# P4-Temperatura_LM35.net
KiCad netlist of a schematic drawn in EAGLE
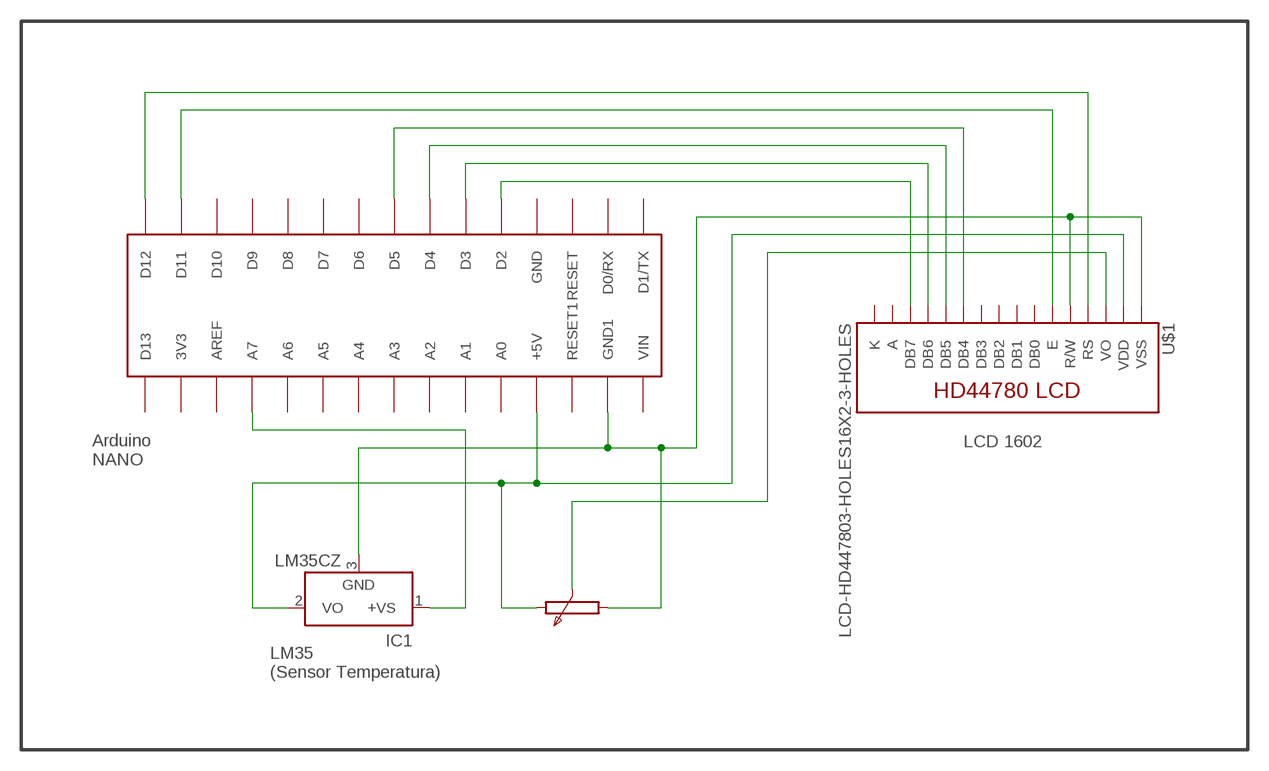
[diagram p0: schematic, sheet 1]

(export (version "E")
  (design (tool "Eeschema 10.0.6"))
  (components
    (comp (ref "IC1")
      (value "LM35CZ")
      (footprint "eagle-import:TO92")
      (libsource (lib "eagle-import") (part "LM35CZ"))
    )
    (comp (ref "U$1")
      (value "LCD-HD447803-HOLES16X2-3-HOLES")
      (footprint "eagle-import:LCD-16X2-3HOLES")
      (libsource (lib "eagle-import") (part "LCD-HD4478016X2-3-HOLES3-HOLES"))
    )
    (comp (ref "U$2")
      (value "ARDUINONANO")
      (footprint "eagle-import:PDIP-32")
      (libsource (lib "eagle-import") (part "ARDUINONANO"))
    )
  )
  (nets
    (net (code "1") (name "/A") (class "Default")
      (node (ref "U$1") (pin "15") (pinfunction "A_15") (pintype "power_in"))
    )
    (net (code "2") (name "/K") (class "Default")
      (node (ref "U$1") (pin "16") (pinfunction "K_16") (pintype "power_in"))
    )
    (net (code "3") (name "Net-(IC1-+VS)") (class "Default")
      (node (ref "IC1") (pin "1") (pinfunction "+VS_1") (pintype "input"))
      (node (ref "U$2") (pin "A7") (pinfunction "A7_A7") (pintype "bidirectional"))
    )
    (net (code "4") (name "Net-(IC1-GND)") (class "Default")
      (node (ref "IC1") (pin "3") (pinfunction "GND_3") (pintype "power_in"))
      (node (ref "U$1") (pin "1") (pinfunction "VSS_1") (pintype "power_in"))
      (node (ref "U$1") (pin "5") (pinfunction "R/W_5") (pintype "input"))
      (node (ref "U$2") (pin "GND1") (pinfunction "GND1_GND1") (pintype "bidirectional"))
    )
    (net (code "5") (name "Net-(IC1-VO)") (class "Default")
      (node (ref "IC1") (pin "2") (pinfunction "VO_2") (pintype "input"))
      (node (ref "U$1") (pin "2") (pinfunction "VDD_2") (pintype "power_in"))
      (node (ref "U$2") (pin "+5V") (pinfunction "+5V_+5V") (pintype "bidirectional"))
    )
    (net (code "6") (name "Net-(U$1-DB4)") (class "Default")
      (node (ref "U$1") (pin "11") (pinfunction "DB4_11") (pintype "bidirectional"))
      (node (ref "U$2") (pin "D5") (pinfunction "D5_D5") (pintype "bidirectional"))
    )
    (net (code "7") (name "Net-(U$1-DB5)") (class "Default")
      (node (ref "U$1") (pin "12") (pinfunction "DB5_12") (pintype "bidirectional"))
      (node (ref "U$2") (pin "D4") (pinfunction "D4_D4") (pintype "bidirectional"))
    )
    (net (code "8") (name "Net-(U$1-DB6)") (class "Default")
      (node (ref "U$1") (pin "13") (pinfunction "DB6_13") (pintype "bidirectional"))
      (node (ref "U$2") (pin "D3") (pinfunction "D3_D3") (pintype "bidirectional"))
    )
    (net (code "9") (name "Net-(U$1-DB7)") (class "Default")
      (node (ref "U$1") (pin "14") (pinfunction "DB7_14") (pintype "bidirectional"))
      (node (ref "U$2") (pin "D2") (pinfunction "D2_D2") (pintype "bidirectional"))
    )
    (net (code "10") (name "Net-(U$1-E)") (class "Default")
      (node (ref "U$1") (pin "6") (pinfunction "E_6") (pintype "input"))
      (node (ref "U$2") (pin "D11") (pinfunction "D11_D11") (pintype "bidirectional"))
    )
    (net (code "11") (name "Net-(U$1-RS)") (class "Default")
      (node (ref "U$1") (pin "4") (pinfunction "RS_4") (pintype "input"))
      (node (ref "U$2") (pin "D12") (pinfunction "D12_D12") (pintype "bidirectional"))
    )
    (net (code "12") (name "unconnected-(U$1-DB0-Pad7)") (class "Default")
      (node (ref "U$1") (pin "7") (pinfunction "DB0_7") (pintype "bidirectional"))
    )
    (net (code "13") (name "unconnected-(U$1-DB1-Pad8)") (class "Default")
      (node (ref "U$1") (pin "8") (pinfunction "DB1_8") (pintype "bidirectional"))
    )
    (net (code "14") (name "unconnected-(U$1-DB2-Pad9)") (class "Default")
      (node (ref "U$1") (pin "9") (pinfunction "DB2_9") (pintype "bidirectional"))
    )
    (net (code "15") (name "unconnected-(U$1-DB3-Pad10)") (class "Default")
      (node (ref "U$1") (pin "10") (pinfunction "DB3_10") (pintype "bidirectional"))
    )
    (net (code "16") (name "unconnected-(U$1-VO-Pad3)") (class "Default")
      (node (ref "U$1") (pin "3") (pinfunction "VO_3") (pintype "bidirectional"))
    )
    (net (code "17") (name "unconnected-(U$2-Pad3V3)") (class "Default")
      (node (ref "U$2") (pin "3V3") (pinfunction "3V3_3V3") (pintype "bidirectional"))
    )
    (net (code "18") (name "unconnected-(U$2-PadA0)") (class "Default")
      (node (ref "U$2") (pin "A0") (pinfunction "A0_A0") (pintype "bidirectional"))
    )
    (net (code "19") (name "unconnected-(U$2-PadA1)") (class "Default")
      (node (ref "U$2") (pin "A1") (pinfunction "A1_A1") (pintype "bidirectional"))
    )
    (net (code "20") (name "unconnected-(U$2-PadA2)") (class "Default")
      (node (ref "U$2") (pin "A2") (pinfunction "A2_A2") (pintype "bidirectional"))
    )
    (net (code "21") (name "unconnected-(U$2-PadA3)") (class "Default")
      (node (ref "U$2") (pin "A3") (pinfunction "A3_A3") (pintype "bidirectional"))
    )
    (net (code "22") (name "unconnected-(U$2-PadA4)") (class "Default")
      (node (ref "U$2") (pin "A4") (pinfunction "A4_A4") (pintype "bidirectional"))
    )
    (net (code "23") (name "unconnected-(U$2-PadA5)") (class "Default")
      (node (ref "U$2") (pin "A5") (pinfunction "A5_A5") (pintype "bidirectional"))
    )
    (net (code "24") (name "unconnected-(U$2-PadA6)") (class "Default")
      (node (ref "U$2") (pin "A6") (pinfunction "A6_A6") (pintype "bidirectional"))
    )
    (net (code "25") (name "unconnected-(U$2-PadAREF)") (class "Default")
      (node (ref "U$2") (pin "AREF") (pinfunction "AREF_AREF") (pintype "bidirectional"))
    )
    (net (code "26") (name "unconnected-(U$2-PadD0{slash}RX)") (class "Default")
      (node (ref "U$2") (pin "D0/RX") (pinfunction "D0/RX_D0/RX") (pintype "bidirectional"))
    )
    (net (code "27") (name "unconnected-(U$2-PadD1{slash}TX)") (class "Default")
      (node (ref "U$2") (pin "D1/TX") (pinfunction "D1/TX_D1/TX") (pintype "bidirectional"))
    )
    (net (code "28") (name "unconnected-(U$2-PadD6)") (class "Default")
      (node (ref "U$2") (pin "D6") (pinfunction "D6_D6") (pintype "bidirectional"))
    )
    (net (code "29") (name "unconnected-(U$2-PadD7)") (class "Default")
      (node (ref "U$2") (pin "D7") (pinfunction "D7_D7") (pintype "bidirectional"))
    )
    (net (code "30") (name "unconnected-(U$2-PadD8)") (class "Default")
      (node (ref "U$2") (pin "D8") (pinfunction "D8_D8") (pintype "bidirectional"))
    )
    (net (code "31") (name "unconnected-(U$2-PadD9)") (class "Default")
      (node (ref "U$2") (pin "D9") (pinfunction "D9_D9") (pintype "bidirectional"))
    )
    (net (code "32") (name "unconnected-(U$2-PadD10)") (class "Default")
      (node (ref "U$2") (pin "D10") (pinfunction "D10_D10") (pintype "bidirectional"))
    )
    (net (code "33") (name "unconnected-(U$2-PadD13)") (class "Default")
      (node (ref "U$2") (pin "D13") (pinfunction "D13_D13") (pintype "bidirectional"))
    )
    (net (code "34") (name "unconnected-(U$2-PadGND)") (class "Default")
      (node (ref "U$2") (pin "GND") (pinfunction "GND_GND") (pintype "bidirectional"))
    )
    (net (code "35") (name "unconnected-(U$2-PadRESET)") (class "Default")
      (node (ref "U$2") (pin "RESET") (pinfunction "RESET_RESET") (pintype "bidirectional"))
    )
    (net (code "36") (name "unconnected-(U$2-PadRESET1)") (class "Default")
      (node (ref "U$2") (pin "RESET1") (pinfunction "RESET1_RESET1") (pintype "bidirectional"))
    )
    (net (code "37") (name "unconnected-(U$2-PadVIN)") (class "Default")
      (node (ref "U$2") (pin "VIN") (pinfunction "VIN_VIN") (pintype "bidirectional"))
    )
  )
)
